# GNSS.net
KiCad netlist of a schematic drawn in Altium Designer
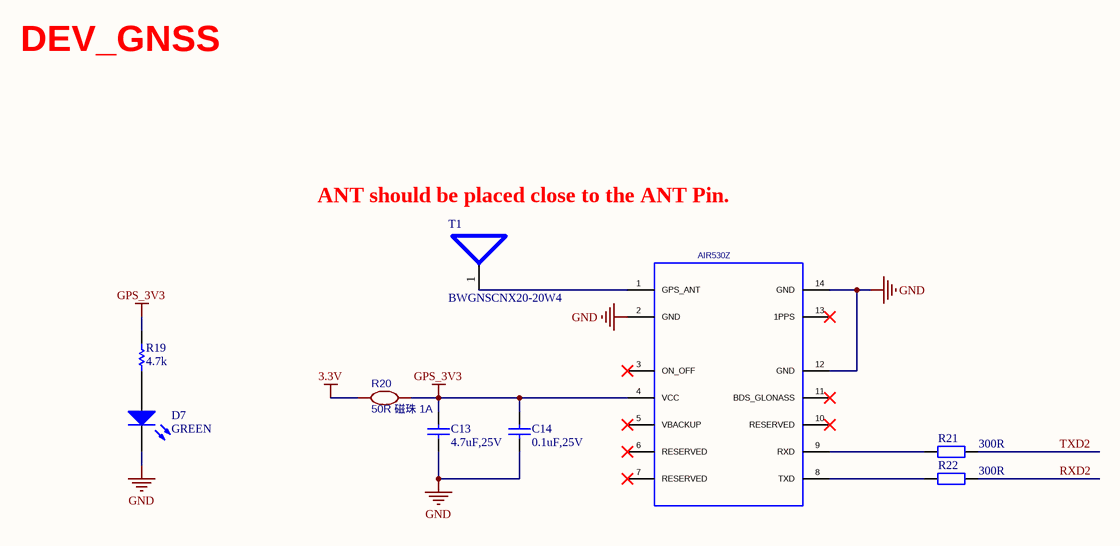
[diagram p0: GNSS.SchDoc]

(export (version "E")
  (design (tool "Eeschema 10.0.6"))
  (components
    (comp (ref "C13")
      (value "4.7uF,25V")
      (footprint "0402_C")
      (description "贴片电容")
      (fields (field (name "PART NUMBER") "T_Cap_0603_0.1uF_25V_X5R") (field (name "TOLERANCE") "10%"))
      (libsource (lib "Database_Library") (part "Cap"))
    )
    (comp (ref "C14")
      (value "0.1uF,25V")
      (footprint "0402_C")
      (description "贴片电容")
      (fields (field (name "PART NUMBER") "T_Cap_0603_0.1uF_25V_X5R") (field (name "TOLERANCE") "10%"))
      (libsource (lib "Database_Library") (part "Cap"))
    )
    (comp (ref "D7")
      (value "GREEN")
      (footprint "0603_LED")
      (description "红色LED灯")
      (fields (field (name "PART NUMBER") "T_LED_Red_0805"))
      (libsource (lib "Database_Library") (part "LED"))
    )
    (comp (ref "R19")
      (value "4.7k")
      (footprint "0603_R")
      (description "贴片电阻")
      (fields (field (name "PART NUMBER") "T_Res_0603_10k_5%_1/10W") (field (name "POWER") "1/10W"))
      (libsource (lib "Database_Library") (part "Res_5%"))
    )
    (comp (ref "R20")
      (value "50R 磁珠 1A")
      (footprint "0402_R")
      (fields (field (name "CONTRIBUTOR") "LCEDA_Lib"))
      (libsource (lib "altium-import") (part "root_2_100k_"))
    )
    (comp (ref "R21")
      (value "300R")
      (footprint "0603_R")
      (description "贴片电阻")
      (fields (field (name "PART NUMBER") "T_Res_0603_49.9k_1%_1/10W") (field (name "POWER") "1/10W"))
      (libsource (lib "Database_Library") (part "Res"))
    )
    (comp (ref "R22")
      (value "300R")
      (footprint "0603_R")
      (description "贴片电阻")
      (fields (field (name "PART NUMBER") "T_Res_0603_49.9k_1%_1/10W") (field (name "POWER") "1/10W"))
      (libsource (lib "Database_Library") (part "Res"))
    )
    (comp (ref "T1")
      (value "BWGNSCNX20-20W4")
      (footprint "ANT-TH_BWGNSCNX20-20W4")
      (libsource (lib "SN_Schlib") (part "ANT"))
    )
    (comp (ref "U5")
      (value "AIR530Z")
      (footprint "AIR530")
      (description "GPS/Beidou/GLONASS module;9.9*12.9*2.3mm")
      (libsource (lib "Board_SN") (part "AIR530Z"))
    )
  )
  (nets
    (net (code "1") (name "/RXD2") (class "Default")
      (node (ref "R22") (pin "2") (pinfunction "2_2") (pintype "passive"))
    )
    (net (code "2") (name "/TXD2") (class "Default")
      (node (ref "R21") (pin "2") (pinfunction "2_2") (pintype "passive"))
    )
    (net (code "3") (name "3.3V") (class "Default")
      (node (ref "R20") (pin "2") (pinfunction "2_2") (pintype "passive"))
    )
    (net (code "4") (name "GND") (class "Default")
      (node (ref "C13") (pin "2") (pinfunction "2_2") (pintype "passive"))
      (node (ref "C14") (pin "2") (pinfunction "2_2") (pintype "passive"))
      (node (ref "D7") (pin "2") (pinfunction "K_2") (pintype "passive"))
      (node (ref "U5") (pin "12") (pinfunction "GND_12") (pintype "passive"))
      (node (ref "U5") (pin "14") (pinfunction "GND_14") (pintype "passive"))
      (node (ref "U5") (pin "2") (pinfunction "GND_2") (pintype "passive"))
    )
    (net (code "5") (name "GPS_3V3") (class "Default")
      (node (ref "C13") (pin "1") (pinfunction "1_1") (pintype "passive"))
      (node (ref "C14") (pin "1") (pinfunction "1_1") (pintype "passive"))
      (node (ref "R19") (pin "2") (pinfunction "2_2") (pintype "passive"))
      (node (ref "R20") (pin "1") (pinfunction "1_1") (pintype "passive"))
      (node (ref "U5") (pin "4") (pinfunction "VCC_4") (pintype "passive"))
    )
    (net (code "6") (name "Net-(D7-A)") (class "Default")
      (node (ref "D7") (pin "1") (pinfunction "A_1") (pintype "passive"))
      (node (ref "R19") (pin "1") (pinfunction "1_1") (pintype "passive"))
    )
    (net (code "7") (name "Net-(U5-GPS_ANT)") (class "Default")
      (node (ref "T1") (pin "1") (pinfunction "1_1") (pintype "passive"))
      (node (ref "U5") (pin "1") (pinfunction "GPS_ANT_1") (pintype "passive"))
    )
    (net (code "8") (name "Net-(U5-RXD)") (class "Default")
      (node (ref "R21") (pin "1") (pinfunction "1_1") (pintype "passive"))
      (node (ref "U5") (pin "9") (pinfunction "RXD_9") (pintype "passive"))
    )
    (net (code "9") (name "Net-(U5-TXD)") (class "Default")
      (node (ref "R22") (pin "1") (pinfunction "1_1") (pintype "passive"))
      (node (ref "U5") (pin "8") (pinfunction "TXD_8") (pintype "passive"))
    )
    (net (code "10") (name "unconnected-(U5-1PPS-Pad13)") (class "Default")
      (node (ref "U5") (pin "13") (pinfunction "1PPS_13") (pintype "passive+no_connect"))
    )
    (net (code "11") (name "unconnected-(U5-BDS_GLONASS-Pad11)") (class "Default")
      (node (ref "U5") (pin "11") (pinfunction "BDS_GLONASS_11") (pintype "passive+no_connect"))
    )
    (net (code "12") (name "unconnected-(U5-ON_OFF-Pad3)") (class "Default")
      (node (ref "U5") (pin "3") (pinfunction "ON_OFF_3") (pintype "passive+no_connect"))
    )
    (net (code "13") (name "unconnected-(U5-RESERVED-Pad6)") (class "Default")
      (node (ref "U5") (pin "6") (pinfunction "RESERVED_6") (pintype "passive+no_connect"))
    )
    (net (code "14") (name "unconnected-(U5-RESERVED-Pad7)") (class "Default")
      (node (ref "U5") (pin "7") (pinfunction "RESERVED_7") (pintype "passive+no_connect"))
    )
    (net (code "15") (name "unconnected-(U5-RESERVED-Pad10)") (class "Default")
      (node (ref "U5") (pin "10") (pinfunction "RESERVED_10") (pintype "passive+no_connect"))
    )
    (net (code "16") (name "unconnected-(U5-VBACKUP-Pad5)") (class "Default")
      (node (ref "U5") (pin "5") (pinfunction "VBACKUP_5") (pintype "passive+no_connect"))
    )
  )
)
